# OSSC_HDMI_Audio_v1_3_A4.net
KiCad netlist of a schematic drawn in EAGLE
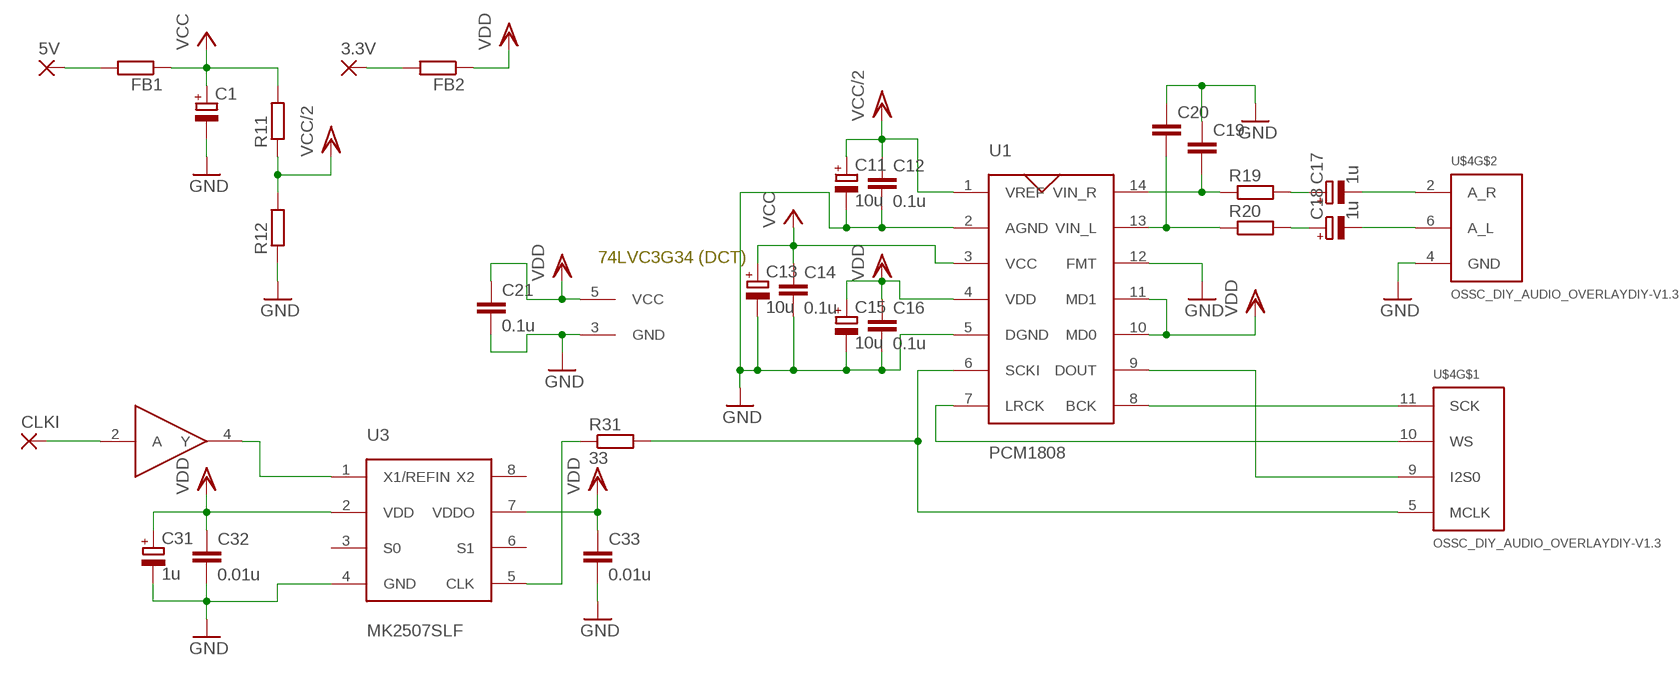
[diagram p0: schematic, sheet 1]

(export (version "E")
  (design (tool "Eeschema 10.0.6"))
  (components
    (comp (ref "3.3V")
      (value "SMD2")
      (footprint "eagle-import:SMD1,27-2,54")
      (libsource (lib "eagle-import") (part "SMD2"))
    )
    (comp (ref "5V")
      (value "SMD2")
      (footprint "eagle-import:SMD1,27-2,54")
      (libsource (lib "eagle-import") (part "SMD2"))
    )
    (comp (ref "C1")
      (value "CPOL-EUSMCC")
      (footprint "eagle-import:SMC_C")
      (libsource (lib "eagle-import") (part "CPOL-EUSMCC"))
    )
    (comp (ref "C11")
      (value "10u")
      (footprint "eagle-import:SMC_A")
      (libsource (lib "eagle-import") (part "CPOL-EUSMCA"))
    )
    (comp (ref "C12")
      (value "0.1u")
      (footprint "eagle-import:C0603")
      (libsource (lib "eagle-import") (part "C-EUC0603"))
    )
    (comp (ref "C13")
      (value "10u")
      (footprint "eagle-import:SMC_A")
      (libsource (lib "eagle-import") (part "CPOL-EUSMCA"))
    )
    (comp (ref "C14")
      (value "0.1u")
      (footprint "eagle-import:C0603")
      (libsource (lib "eagle-import") (part "C-EUC0603"))
    )
    (comp (ref "C15")
      (value "10u")
      (footprint "eagle-import:SMC_A")
      (libsource (lib "eagle-import") (part "CPOL-EUSMCA"))
    )
    (comp (ref "C16")
      (value "0.1u")
      (footprint "eagle-import:C0603")
      (libsource (lib "eagle-import") (part "C-EUC0603"))
    )
    (comp (ref "C17")
      (value "1u")
      (footprint "eagle-import:SMC_A")
      (libsource (lib "eagle-import") (part "CPOL-EUSMCA"))
    )
    (comp (ref "C18")
      (value "1u")
      (footprint "eagle-import:SMC_A")
      (libsource (lib "eagle-import") (part "CPOL-EUSMCA"))
    )
    (comp (ref "C19")
      (value "C-EUC0603")
      (footprint "eagle-import:C0603")
      (libsource (lib "eagle-import") (part "C-EUC0603"))
    )
    (comp (ref "C20")
      (value "C-EUC0603")
      (footprint "eagle-import:C0603")
      (libsource (lib "eagle-import") (part "C-EUC0603"))
    )
    (comp (ref "C21")
      (value "0.1u")
      (footprint "eagle-import:C0603")
      (libsource (lib "eagle-import") (part "C-EUC0603"))
    )
    (comp (ref "C31")
      (value "1u")
      (footprint "eagle-import:SMC_A")
      (libsource (lib "eagle-import") (part "CPOL-EUSMCA"))
    )
    (comp (ref "C32")
      (value "0.01u")
      (footprint "eagle-import:C0603")
      (libsource (lib "eagle-import") (part "C-EUC0603"))
    )
    (comp (ref "C33")
      (value "0.01u")
      (footprint "eagle-import:C0603")
      (libsource (lib "eagle-import") (part "C-EUC0603"))
    )
    (comp (ref "CLKI")
      (value "SMD2")
      (footprint "eagle-import:SMD1,27-2,54")
      (libsource (lib "eagle-import") (part "SMD2"))
    )
    (comp (ref "FB1")
      (value "R-EU_R0603")
      (footprint "eagle-import:R0603")
      (libsource (lib "eagle-import") (part "R-EU_R0603"))
    )
    (comp (ref "FB2")
      (value "R-EU_R0603")
      (footprint "eagle-import:R0603")
      (libsource (lib "eagle-import") (part "R-EU_R0603"))
    )
    (comp (ref "R11")
      (value "R-EU_R0603")
      (footprint "eagle-import:R0603")
      (libsource (lib "eagle-import") (part "R-EU_R0603"))
    )
    (comp (ref "R12")
      (value "R-EU_R0603")
      (footprint "eagle-import:R0603")
      (libsource (lib "eagle-import") (part "R-EU_R0603"))
    )
    (comp (ref "R19")
      (value "R-EU_R0603")
      (footprint "eagle-import:R0603")
      (libsource (lib "eagle-import") (part "R-EU_R0603"))
    )
    (comp (ref "R20")
      (value "R-EU_R0603")
      (footprint "eagle-import:R0603")
      (libsource (lib "eagle-import") (part "R-EU_R0603"))
    )
    (comp (ref "R31")
      (value "33")
      (footprint "eagle-import:R0603")
      (libsource (lib "eagle-import") (part "R-EU_R0603"))
    )
    (comp (ref "U$4")
      (value "OSSC_DIY_AUDIO_OVERLAYDIY-V1.3")
      (footprint "eagle-import:OSSC_OVERLAY_V1.3")
      (libsource (lib "eagle-import") (part "OSSC_DIY_AUDIO_OVERLAYDIY-V1.3"))
    )
    (comp (ref "U1")
      (value "PCM1808")
      (footprint "eagle-import:PCM1808")
      (libsource (lib "eagle-import") (part "PCM1808"))
    )
    (comp (ref "U2")
      (value "74LVC1G34")
      (footprint "eagle-import:74LVC1G34DCK")
      (libsource (lib "eagle-import") (part "74LVC1G34"))
    )
    (comp (ref "U3")
      (value "MK2507SLF")
      (footprint "eagle-import:SOIC8")
      (libsource (lib "eagle-import") (part "MK2507SLF"))
    )
  )
  (nets
    (net (code "1") (name "GND") (class "Default")
      (node (ref "C1") (pin "-") (pinfunction "-_-") (pintype "passive"))
      (node (ref "C11") (pin "-") (pinfunction "-_-") (pintype "passive"))
      (node (ref "C12") (pin "2") (pinfunction "2_2") (pintype "passive"))
      (node (ref "C13") (pin "-") (pinfunction "-_-") (pintype "passive"))
      (node (ref "C14") (pin "2") (pinfunction "2_2") (pintype "passive"))
      (node (ref "C15") (pin "-") (pinfunction "-_-") (pintype "passive"))
      (node (ref "C16") (pin "2") (pinfunction "2_2") (pintype "passive"))
      (node (ref "C19") (pin "1") (pinfunction "1_1") (pintype "passive"))
      (node (ref "C20") (pin "1") (pinfunction "1_1") (pintype "passive"))
      (node (ref "C21") (pin "2") (pinfunction "2_2") (pintype "passive"))
      (node (ref "C31") (pin "-") (pinfunction "-_-") (pintype "passive"))
      (node (ref "C32") (pin "2") (pinfunction "2_2") (pintype "passive"))
      (node (ref "C33") (pin "2") (pinfunction "2_2") (pintype "passive"))
      (node (ref "R12") (pin "1") (pinfunction "1_1") (pintype "passive"))
      (node (ref "U$4") (pin "4") (pinfunction "GND_4") (pintype "bidirectional"))
      (node (ref "U1") (pin "12") (pinfunction "FMT_12") (pintype "bidirectional"))
      (node (ref "U1") (pin "2") (pinfunction "AGND_2") (pintype "bidirectional"))
      (node (ref "U1") (pin "5") (pinfunction "DGND_5") (pintype "bidirectional"))
      (node (ref "U2") (pin "3") (pinfunction "GND_3") (pintype "bidirectional"))
      (node (ref "U3") (pin "4") (pinfunction "GND_4") (pintype "bidirectional"))
    )
    (net (code "2") (name "Net-(3.3V-P)") (class "Default")
      (node (ref "3.3V") (pin "1") (pinfunction "P_1") (pintype "passive"))
      (node (ref "FB2") (pin "2") (pinfunction "2_2") (pintype "passive"))
    )
    (net (code "3") (name "Net-(5V-P)") (class "Default")
      (node (ref "5V") (pin "1") (pinfunction "P_1") (pintype "passive"))
      (node (ref "FB1") (pin "2") (pinfunction "2_2") (pintype "passive"))
    )
    (net (code "4") (name "Net-(C17-Pad+)") (class "Default")
      (node (ref "C17") (pin "+") (pinfunction "+_+") (pintype "passive"))
      (node (ref "R19") (pin "2") (pinfunction "2_2") (pintype "passive"))
    )
    (net (code "5") (name "Net-(C18-Pad+)") (class "Default")
      (node (ref "C18") (pin "+") (pinfunction "+_+") (pintype "passive"))
      (node (ref "R20") (pin "2") (pinfunction "2_2") (pintype "passive"))
    )
    (net (code "6") (name "Net-(CLKI-P)") (class "Default")
      (node (ref "CLKI") (pin "1") (pinfunction "P_1") (pintype "passive"))
      (node (ref "U2") (pin "2") (pinfunction "A_2") (pintype "bidirectional"))
    )
    (net (code "7") (name "Net-(U$4A-I2S0)") (class "Default")
      (node (ref "U$4") (pin "9") (pinfunction "I2S0_9") (pintype "bidirectional"))
      (node (ref "U1") (pin "9") (pinfunction "DOUT_9") (pintype "bidirectional"))
    )
    (net (code "8") (name "Net-(U$4A-MCLK)") (class "Default")
      (node (ref "R31") (pin "2") (pinfunction "2_2") (pintype "passive"))
      (node (ref "U$4") (pin "5") (pinfunction "MCLK_5") (pintype "bidirectional"))
      (node (ref "U1") (pin "6") (pinfunction "SCKI_6") (pintype "bidirectional"))
    )
    (net (code "9") (name "Net-(U$4A-SCK)") (class "Default")
      (node (ref "U$4") (pin "11") (pinfunction "SCK_11") (pintype "bidirectional"))
      (node (ref "U1") (pin "8") (pinfunction "BCK_8") (pintype "bidirectional"))
    )
    (net (code "10") (name "Net-(U$4A-WS)") (class "Default")
      (node (ref "U$4") (pin "10") (pinfunction "WS_10") (pintype "bidirectional"))
      (node (ref "U1") (pin "7") (pinfunction "LRCK_7") (pintype "bidirectional"))
    )
    (net (code "11") (name "Net-(U$4B-A_L)") (class "Default")
      (node (ref "C18") (pin "-") (pinfunction "-_-") (pintype "passive"))
      (node (ref "U$4") (pin "6") (pinfunction "A_L_6") (pintype "bidirectional"))
    )
    (net (code "12") (name "Net-(U$4B-A_R)") (class "Default")
      (node (ref "C17") (pin "-") (pinfunction "-_-") (pintype "passive"))
      (node (ref "U$4") (pin "2") (pinfunction "A_R_2") (pintype "bidirectional"))
    )
    (net (code "13") (name "Net-(U1-VIN_L)") (class "Default")
      (node (ref "C20") (pin "2") (pinfunction "2_2") (pintype "passive"))
      (node (ref "R20") (pin "1") (pinfunction "1_1") (pintype "passive"))
      (node (ref "U1") (pin "13") (pinfunction "VIN_L_13") (pintype "bidirectional"))
    )
    (net (code "14") (name "Net-(U1-VIN_R)") (class "Default")
      (node (ref "C19") (pin "2") (pinfunction "2_2") (pintype "passive"))
      (node (ref "R19") (pin "1") (pinfunction "1_1") (pintype "passive"))
      (node (ref "U1") (pin "14") (pinfunction "VIN_R_14") (pintype "bidirectional"))
    )
    (net (code "15") (name "Net-(U2A-Y)") (class "Default")
      (node (ref "U2") (pin "4") (pinfunction "Y_4") (pintype "bidirectional"))
      (node (ref "U3") (pin "1") (pinfunction "X1/REFIN_1") (pintype "bidirectional"))
    )
    (net (code "16") (name "Net-(U3-CLK)") (class "Default")
      (node (ref "R31") (pin "1") (pinfunction "1_1") (pintype "passive"))
      (node (ref "U3") (pin "5") (pinfunction "CLK_5") (pintype "bidirectional"))
    )
    (net (code "17") (name "VCC") (class "Default")
      (node (ref "C1") (pin "+") (pinfunction "+_+") (pintype "passive"))
      (node (ref "C13") (pin "+") (pinfunction "+_+") (pintype "passive"))
      (node (ref "C14") (pin "1") (pinfunction "1_1") (pintype "passive"))
      (node (ref "FB1") (pin "1") (pinfunction "1_1") (pintype "passive"))
      (node (ref "R11") (pin "2") (pinfunction "2_2") (pintype "passive"))
      (node (ref "U1") (pin "3") (pinfunction "VCC_3") (pintype "bidirectional"))
    )
    (net (code "18") (name "VCC{slash}2") (class "Default")
      (node (ref "C11") (pin "+") (pinfunction "+_+") (pintype "passive"))
      (node (ref "C12") (pin "1") (pinfunction "1_1") (pintype "passive"))
      (node (ref "R11") (pin "1") (pinfunction "1_1") (pintype "passive"))
      (node (ref "R12") (pin "2") (pinfunction "2_2") (pintype "passive"))
      (node (ref "U1") (pin "1") (pinfunction "VREF_1") (pintype "bidirectional"))
    )
    (net (code "19") (name "VDD") (class "Default")
      (node (ref "C15") (pin "+") (pinfunction "+_+") (pintype "passive"))
      (node (ref "C16") (pin "1") (pinfunction "1_1") (pintype "passive"))
      (node (ref "C21") (pin "1") (pinfunction "1_1") (pintype "passive"))
      (node (ref "C31") (pin "+") (pinfunction "+_+") (pintype "passive"))
      (node (ref "C32") (pin "1") (pinfunction "1_1") (pintype "passive"))
      (node (ref "C33") (pin "1") (pinfunction "1_1") (pintype "passive"))
      (node (ref "FB2") (pin "1") (pinfunction "1_1") (pintype "passive"))
      (node (ref "U1") (pin "10") (pinfunction "MD0_10") (pintype "bidirectional"))
      (node (ref "U1") (pin "11") (pinfunction "MD1_11") (pintype "bidirectional"))
      (node (ref "U1") (pin "4") (pinfunction "VDD_4") (pintype "bidirectional"))
      (node (ref "U2") (pin "5") (pinfunction "VCC_5") (pintype "bidirectional"))
      (node (ref "U3") (pin "2") (pinfunction "VDD_2") (pintype "bidirectional"))
      (node (ref "U3") (pin "7") (pinfunction "VDDO_7") (pintype "bidirectional"))
    )
    (net (code "20") (name "unconnected-(U3-S0-Pad3)") (class "Default")
      (node (ref "U3") (pin "3") (pinfunction "S0_3") (pintype "bidirectional"))
    )
    (net (code "21") (name "unconnected-(U3-S1-Pad6)") (class "Default")
      (node (ref "U3") (pin "6") (pinfunction "S1_6") (pintype "bidirectional"))
    )
    (net (code "22") (name "unconnected-(U3-X2-Pad8)") (class "Default")
      (node (ref "U3") (pin "8") (pinfunction "X2_8") (pintype "bidirectional"))
    )
  )
)
